# 3V3_LD1117S33TR.net
KiCad netlist of a schematic drawn in Altium Designer
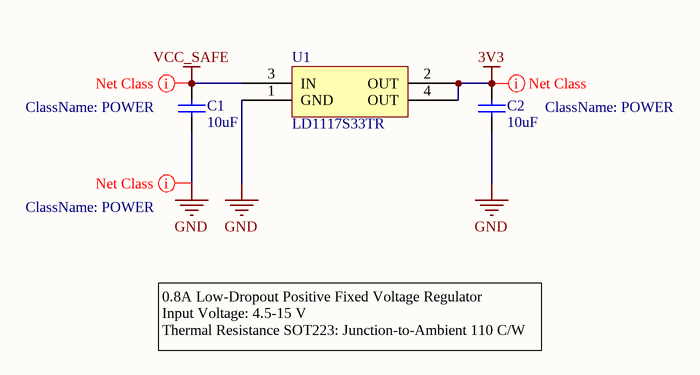
[diagram p0: 3V3 LD1117S33TR.SchDoc]

(export (version "E")
  (design (tool "Eeschema 10.0.6"))
  (components
    (comp (ref "C1")
      (value "10uF")
      (footprint "agh_racing_2018:CAP_0603_IPC_MD")
      (description "Capacitor")
      (fields (field (name "Comment") "Cap"))
      (libsource (lib "agh_racing_2018") (part "Cap"))
    )
    (comp (ref "C2")
      (value "10uF")
      (footprint "agh_racing_2018:CAP_0603_IPC_MD")
      (description "Capacitor")
      (fields (field (name "Comment") "Cap"))
      (libsource (lib "agh_racing_2018") (part "Cap"))
    )
    (comp (ref "U1")
      (value "LD1117S33TR")
      (footprint "agh_racing_2018:SOT223_IPC_HD")
      (libsource (lib "agh_racing_2018") (part "LD1117S33TR"))
    )
  )
  (nets
    (net (code "1") (name "3V3") (class "Default")
      (node (ref "C2") (pin "2") (pinfunction "2_2") (pintype "passive"))
      (node (ref "U1") (pin "2") (pinfunction "OUT_2") (pintype "power_in"))
      (node (ref "U1") (pin "4") (pinfunction "OUT_4") (pintype "power_in"))
    )
    (net (code "2") (name "GND") (class "Default")
      (node (ref "C1") (pin "1") (pinfunction "1_1") (pintype "passive"))
      (node (ref "C2") (pin "1") (pinfunction "1_1") (pintype "passive"))
      (node (ref "U1") (pin "1") (pinfunction "GND_1") (pintype "power_in"))
    )
    (net (code "3") (name "VCC_SAFE") (class "Default")
      (node (ref "C1") (pin "2") (pinfunction "2_2") (pintype "passive"))
      (node (ref "U1") (pin "3") (pinfunction "IN_3") (pintype "power_in"))
    )
  )
)
